# ProPrj_2025f4_025-07-20.net
KiCad netlist of a schematic drawn in EasyEDA Pro
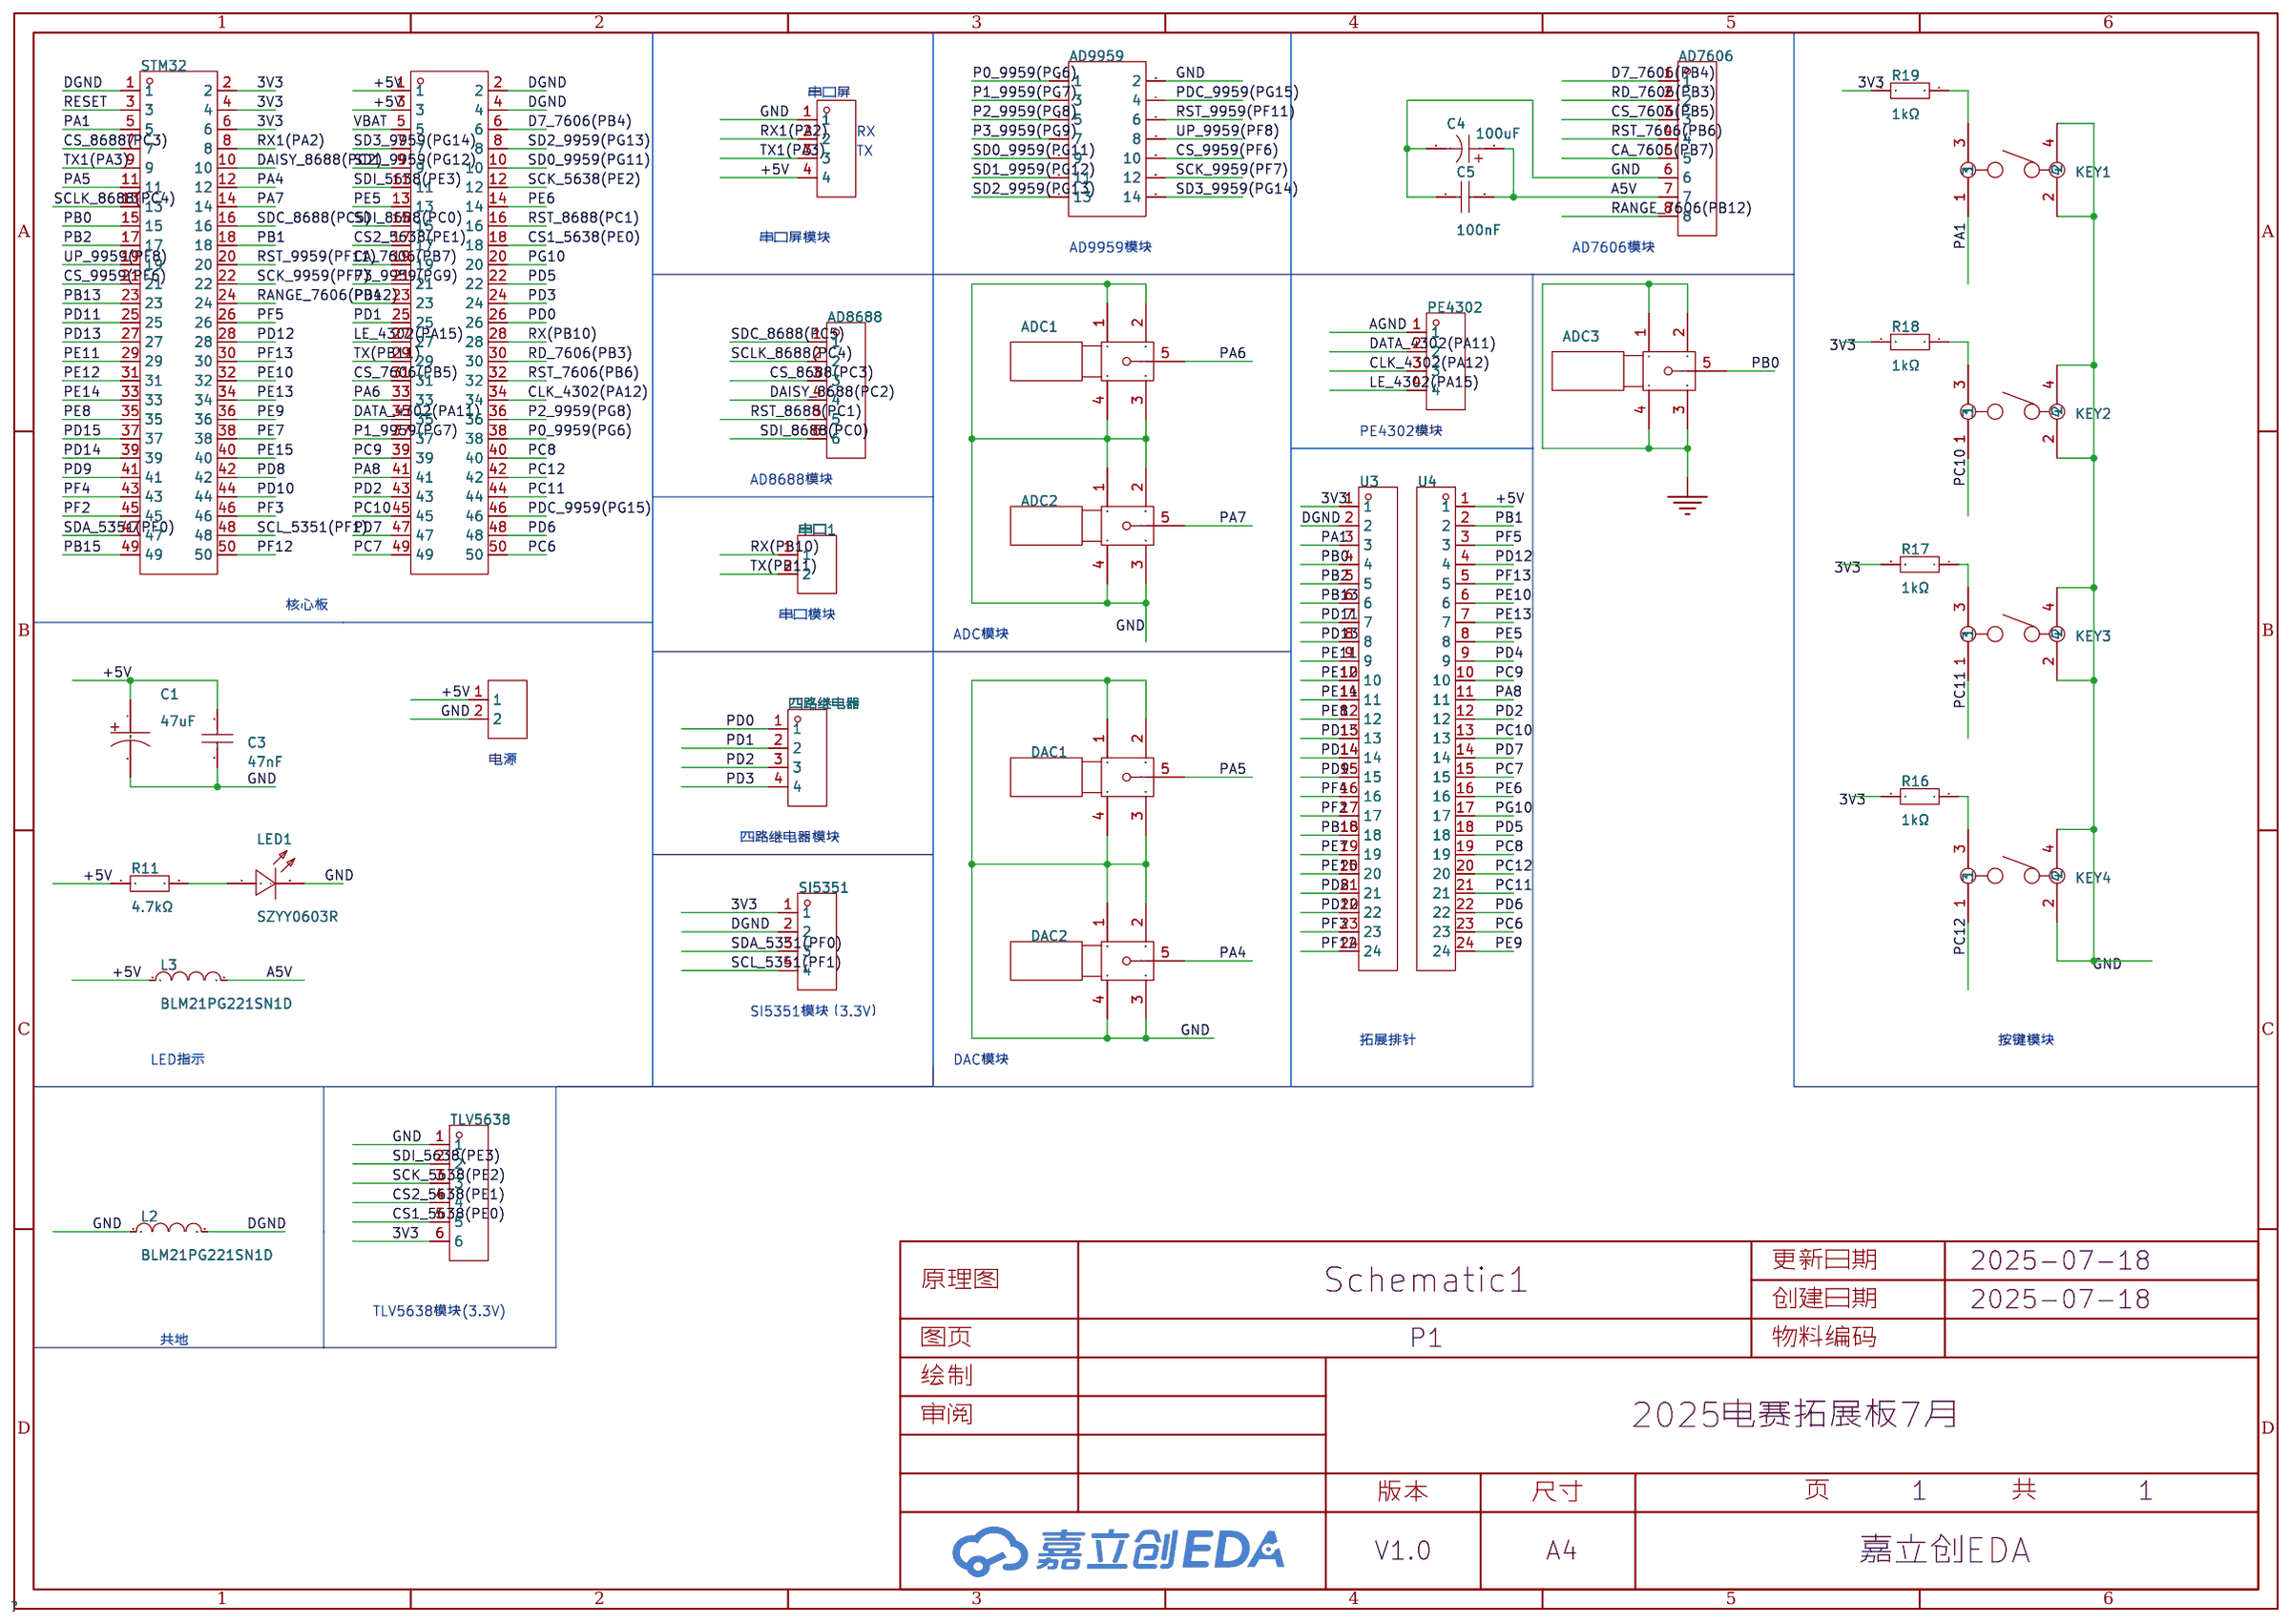
[diagram p0: schematic sheet]

(export (version "E")
  (design (tool "Eeschema 10.0.6"))
  (components
    (comp (ref "AD7606")
      (value "ZX-XH2.54-8PZZ")
      (footprint "easyedapro:CONN-TH_8P-P2.50-XH2.54-8P")
      (fields (field (name "Manufacturer") "Megastar(兆星)"))
      (libsource (lib "easyedapro") (part "ZX-XH2.54-8PZZ"))
    )
    (comp (ref "AD8688")
      (value "ZX-XH2.54-6PZZ")
      (footprint "easyedapro:CONN-TH_6P-P2.50_ZX-XH2.54-6PZZ")
      (fields (field (name "Manufacturer") "Megastar(兆星)"))
      (libsource (lib "easyedapro") (part "ZX-XH2.54-6PZZ"))
    )
    (comp (ref "AD9959")
      (value "2.54-2*7P简牛")
      (footprint "easyedapro:IDC-TH_14P-P2.54-V-R2-C7-S2.54")
      (description "连接器类型:简牛座;间距:2.54mm;结构:2x7P;封装形式:直插;行距:2.54mm;排数:2;每排PIN数:7;触头材质:黄铜;触头镀层:金;")
      (fields (field (name "Manufacturer") "BOOMELE(博穆精密)"))
      (libsource (lib "easyedapro") (part "HDR-IDC-2.54-2X7P"))
    )
    (comp (ref "ADC1")
      (value "BWSMA-KE-P001")
      (footprint "easyedapro:SMA-SMD_BWSMA-KE-P001")
      (description "连接器类型:板端;接口类型:内孔;端口数量:1;接口直径:5.2mm;接口长度/高度:-;频率-最大值:-;射频系列:SMA;阻抗:50Ω;样式:偏脚;工作温度范围:-;")
      (fields (field (name "Manufacturer") "BAT WIRELESS(蝙蝠无线)"))
      (libsource (lib "easyedapro") (part "BWSMA-KE-P001"))
    )
    (comp (ref "ADC2")
      (value "BWSMA-KE-P001")
      (footprint "easyedapro:SMA-SMD_BWSMA-KE-P001")
      (description "连接器类型:板端;接口类型:内孔;端口数量:1;接口直径:5.2mm;接口长度/高度:-;频率-最大值:-;射频系列:SMA;阻抗:50Ω;样式:偏脚;工作温度范围:-;")
      (fields (field (name "Manufacturer") "BAT WIRELESS(蝙蝠无线)"))
      (libsource (lib "easyedapro") (part "BWSMA-KE-P001"))
    )
    (comp (ref "ADC3")
      (value "BWSMA-KE-P001")
      (footprint "easyedapro:SMA-SMD_BWSMA-KE-P001")
      (description "连接器类型:板端;接口类型:内孔;端口数量:1;接口直径:5.2mm;接口长度/高度:-;频率-最大值:-;射频系列:SMA;阻抗:50Ω;样式:偏脚;工作温度范围:-;")
      (fields (field (name "Manufacturer") "BAT WIRELESS(蝙蝠无线)"))
      (libsource (lib "easyedapro") (part "BWSMA-KE-P001"))
    )
    (comp (ref "C1")
      (value "47uF")
      (footprint "easyedapro:CAP-TH_BD5.0-P2.00-D0.8-FD")
      (description "容值:47uF;精度:±20%;额定电压:25V;纹波电流:250mA@100kHz;等效串联电阻(ESR):300mΩ@100kHz;")
      (fields
        (field (name "Manufacturer Part") "NXB25V47M5*11 2.5TP")
        (field (name "Manufacturer") "SAMYOUNG(韩国三莹)")
      )
      (libsource (lib "easyedapro") (part "NXB25VB47M5*11_2.5TP"))
    )
    (comp (ref "C3")
      (value "47nF")
      (footprint "easyedapro:C0805")
      (description "容值:47nF;精度:±10%;额定电压:50V;材质(温度系数):X7R;")
      (fields
        (field (name "Manufacturer Part") "CL21B473KBCNNNC")
        (field (name "Manufacturer") "SAMSUNG(三星)")
      )
      (libsource (lib "easyedapro") (part "CL21B473KBCNNNC"))
    )
    (comp (ref "C4")
      (value "100uF")
      (footprint "easyedapro:CAP-TH_BD8.0-P3.50-D0.5-FD")
      (description "容值:100uF;精度:±20%;额定电压:50V;纹波电流:680mA@120Hz;等效串联电阻(ESR):120mΩ;")
      (fields (field (name "Manufacturer Part") "ERG50V100M8X12") (field (name "Manufacturer") "捷而瑞"))
      (libsource (lib "easyedapro") (part "ERG50V100M8X12"))
    )
    (comp (ref "C5")
      (value "100nF")
      (footprint "easyedapro:C0805")
      (description "容值:100nF;精度:±10%;额定电压:50V;材质(温度系数):X7R;")
      (fields
        (field (name "Manufacturer Part") "CL21B104KBCNNNC")
        (field (name "Manufacturer") "SAMSUNG(三星)")
      )
      (libsource (lib "easyedapro") (part "CL21B104KBCNNNC"))
    )
    (comp (ref "DAC1")
      (value "BWSMA-KE-P001")
      (footprint "easyedapro:SMA-SMD_BWSMA-KE-P001")
      (description "连接器类型:板端;接口类型:内孔;端口数量:1;接口直径:5.2mm;接口长度/高度:-;频率-最大值:-;射频系列:SMA;阻抗:50Ω;样式:偏脚;工作温度范围:-;")
      (fields (field (name "Manufacturer") "BAT WIRELESS(蝙蝠无线)"))
      (libsource (lib "easyedapro") (part "BWSMA-KE-P001"))
    )
    (comp (ref "DAC2")
      (value "BWSMA-KE-P001")
      (footprint "easyedapro:SMA-SMD_BWSMA-KE-P001")
      (description "连接器类型:板端;接口类型:内孔;端口数量:1;接口直径:5.2mm;接口长度/高度:-;频率-最大值:-;射频系列:SMA;阻抗:50Ω;样式:偏脚;工作温度范围:-;")
      (fields (field (name "Manufacturer") "BAT WIRELESS(蝙蝠无线)"))
      (libsource (lib "easyedapro") (part "BWSMA-KE-P001"))
    )
    (comp (ref "KEY1")
      (value "~")
      (footprint "easyedapro:4角直插式开关")
      (description "4.5*4.5*3.8")
      (libsource (lib "easyedapro") (part "4角直插式开关"))
    )
    (comp (ref "KEY2")
      (value "~")
      (footprint "easyedapro:4角直插式开关")
      (description "4.5*4.5*3.8")
      (libsource (lib "easyedapro") (part "4角直插式开关"))
    )
    (comp (ref "KEY3")
      (value "~")
      (footprint "easyedapro:4角直插式开关")
      (description "4.5*4.5*3.8")
      (libsource (lib "easyedapro") (part "4角直插式开关"))
    )
    (comp (ref "KEY4")
      (value "~")
      (footprint "easyedapro:4角直插式开关")
      (description "4.5*4.5*3.8")
      (libsource (lib "easyedapro") (part "4角直插式开关"))
    )
    (comp (ref "L2")
      (value "BLM21PG221SN1D")
      (footprint "easyedapro:L0805")
      (description "标称阻抗@测试频率:220Ω@100MHz;误差:±25%;直流电阻(RDC):45mΩ;")
      (fields (field (name "Manufacturer") "muRata(村田)"))
      (libsource (lib "easyedapro") (part "BLM21PG221SN1D"))
    )
    (comp (ref "L3")
      (value "BLM21PG221SN1D")
      (footprint "easyedapro:L0805")
      (description "标称阻抗@测试频率:220Ω@100MHz;误差:±25%;直流电阻(RDC):45mΩ;")
      (fields (field (name "Manufacturer") "muRata(村田)"))
      (libsource (lib "easyedapro") (part "BLM21PG221SN1D"))
    )
    (comp (ref "LED1")
      (value "SZYY0603R")
      (footprint "easyedapro:LED0603-R-RD")
      (fields (field (name "Manufacturer") "yongyu(永裕光电)"))
      (libsource (lib "easyedapro") (part "SZYY0603R"))
    )
    (comp (ref "OLED显示屏模块2")
      (value "ZX-XH2.54-4PZZ")
      (footprint "easyedapro:CONN-TH_4P-P2.50_4PIN")
      (fields (field (name "Manufacturer") "Megastar(兆星)"))
      (libsource (lib "easyedapro") (part "ZX-XH2.54-4PZZ"))
    )
    (comp (ref "PE4302")
      (value "ZX-XH2.54-4PZZ")
      (footprint "easyedapro:CONN-TH_4P-P2.50_4PIN")
      (fields (field (name "Manufacturer") "Megastar(兆星)"))
      (libsource (lib "easyedapro") (part "ZX-XH2.54-4PZZ"))
    )
    (comp (ref "R11")
      (value "4.7kΩ")
      (footprint "easyedapro:R0805")
      (description "电阻类型:厚膜电阻;阻值:4.7kΩ;精度:±1%;功率:125mW;最大工作电压:150V;温度系数:±100ppm/°C;")
      (fields
        (field (name "Manufacturer Part") "0805W8F4701T5E")
        (field (name "Manufacturer") "UNI-ROYAL(厚声)")
      )
      (libsource (lib "easyedapro") (part "0805W8F4701T5E"))
    )
    (comp (ref "R16")
      (value "1kΩ")
      (footprint "easyedapro:R0805")
      (description "电阻类型:厚膜电阻;阻值:1kΩ;精度:±1%;功率:125mW;温度系数:±100ppm/°C;最大工作电压:150V;工作温度范围:-55°C~+155°C;")
      (fields
        (field (name "Manufacturer Part") "0805W8F1001T5E")
        (field (name "Manufacturer") "UNI-ROYAL(厚声)")
      )
      (libsource (lib "easyedapro") (part "0805W8F1001T5E"))
    )
    (comp (ref "R17")
      (value "1kΩ")
      (footprint "easyedapro:R0805")
      (description "电阻类型:厚膜电阻;阻值:1kΩ;精度:±1%;功率:125mW;温度系数:±100ppm/°C;最大工作电压:150V;工作温度范围:-55°C~+155°C;")
      (fields
        (field (name "Manufacturer Part") "0805W8F1001T5E")
        (field (name "Manufacturer") "UNI-ROYAL(厚声)")
      )
      (libsource (lib "easyedapro") (part "0805W8F1001T5E"))
    )
    (comp (ref "R18")
      (value "1kΩ")
      (footprint "easyedapro:R0805")
      (description "电阻类型:厚膜电阻;阻值:1kΩ;精度:±1%;功率:125mW;温度系数:±100ppm/°C;最大工作电压:150V;工作温度范围:-55°C~+155°C;")
      (fields
        (field (name "Manufacturer Part") "0805W8F1001T5E")
        (field (name "Manufacturer") "UNI-ROYAL(厚声)")
      )
      (libsource (lib "easyedapro") (part "0805W8F1001T5E"))
    )
    (comp (ref "R19")
      (value "1kΩ")
      (footprint "easyedapro:R0805")
      (description "电阻类型:厚膜电阻;阻值:1kΩ;精度:±1%;功率:125mW;温度系数:±100ppm/°C;最大工作电压:150V;工作温度范围:-55°C~+155°C;")
      (fields
        (field (name "Manufacturer Part") "0805W8F1001T5E")
        (field (name "Manufacturer") "UNI-ROYAL(厚声)")
      )
      (libsource (lib "easyedapro") (part "0805W8F1001T5E"))
    )
    (comp (ref "SI5351")
      (value "ZX-XH2.54-4PZZ")
      (footprint "easyedapro:CONN-TH_4P-P2.50_4PIN")
      (fields (field (name "Manufacturer") "Megastar(兆星)"))
      (libsource (lib "easyedapro") (part "ZX-XH2.54-4PZZ"))
    )
    (comp (ref "STM32")
      (value "ZX-PM2.54-2-25PY")
      (footprint "easyedapro:HDR-TH_50P-P2.54-V-F-R2-C25-S2.54-1")
      (fields (field (name "Manufacturer") "Megastar(兆星)"))
      (libsource (lib "easyedapro") (part "ZX-PM2.54-2-25PY"))
    )
    (comp (ref "TLV5638")
      (value "ZX-XH2.54-6PZZ")
      (footprint "easyedapro:CONN-TH_6P-P2.50_ZX-XH2.54-6PZZ")
      (fields (field (name "Manufacturer") "Megastar(兆星)"))
      (libsource (lib "easyedapro") (part "ZX-XH2.54-6PZZ"))
    )
    (comp (ref "U2")
      (value "ZX-PM2.54-2-25PY")
      (footprint "easyedapro:HDR-TH_50P-P2.54-V-F-R2-C25-S2.54-1")
      (fields (field (name "Manufacturer") "Megastar(兆星)"))
      (libsource (lib "easyedapro") (part "ZX-PM2.54-2-25PY"))
    )
    (comp (ref "U3")
      (value "HC-PM254-8.5H-1x24PZ")
      (footprint "easyedapro:HDR-TH_24P-P2.54-V-F")
      (fields (field (name "Manufacturer") "HC(虹成电子)"))
      (libsource (lib "easyedapro") (part "HC-PM254-8.5H-1X24PZ"))
    )
    (comp (ref "U4")
      (value "HC-PM254-8.5H-1x24PZ")
      (footprint "easyedapro:HDR-TH_24P-P2.54-V-F")
      (fields (field (name "Manufacturer") "HC(虹成电子)"))
      (libsource (lib "easyedapro") (part "HC-PM254-8.5H-1X24PZ"))
    )
    (comp (ref "串口")
      (value "ZX-XH2.54-2PZZ")
      (footprint "easyedapro:CONN-TH_2P-P2.50_HX25003-2A")
      (fields (field (name "Manufacturer") "Megastar(兆星)"))
      (libsource (lib "easyedapro") (part "ZX-XH2.54-2PZZ"))
    )
    (comp (ref "串口1")
      (value "ZX-XH2.54-2PZZ")
      (footprint "easyedapro:CONN-TH_2P-P2.50_HX25003-2A")
      (fields (field (name "Manufacturer") "Megastar(兆星)"))
      (libsource (lib "easyedapro") (part "ZX-XH2.54-2PZZ"))
    )
    (comp (ref "四路继电器")
      (value "ZX-XH2.54-4PZZ")
      (footprint "easyedapro:CONN-TH_4P-P2.50_4PIN")
      (fields (field (name "Manufacturer") "Megastar(兆星)"))
      (libsource (lib "easyedapro") (part "ZX-XH2.54-4PZZ"))
    )
  )
  (nets
    (net (code "1") (name "/+5V") (class "Default")
      (node (ref "C1") (pin "1") (pinfunction "1_1") (pintype "unspecified"))
      (node (ref "C3") (pin "2") (pinfunction "2_2") (pintype "input"))
      (node (ref "L3") (pin "1") (pinfunction "1_1") (pintype "unspecified"))
      (node (ref "OLED显示屏模块2") (pin "4") (pinfunction "4_4") (pintype "unspecified"))
      (node (ref "R11") (pin "1") (pinfunction "1_1") (pintype "input"))
      (node (ref "U2") (pin "1") (pinfunction "1_1") (pintype "unspecified"))
      (node (ref "U2") (pin "3") (pinfunction "3_3") (pintype "unspecified"))
      (node (ref "U4") (pin "1") (pinfunction "1_1") (pintype "unspecified"))
      (node (ref "串口") (pin "1") (pinfunction "1_1") (pintype "unspecified"))
    )
    (net (code "2") (name "/3V3") (class "Default")
      (node (ref "R16") (pin "2") (pinfunction "2_2") (pintype "input"))
      (node (ref "R17") (pin "2") (pinfunction "2_2") (pintype "input"))
      (node (ref "R18") (pin "2") (pinfunction "2_2") (pintype "input"))
      (node (ref "R19") (pin "2") (pinfunction "2_2") (pintype "input"))
      (node (ref "SI5351") (pin "1") (pinfunction "1_1") (pintype "unspecified"))
      (node (ref "STM32") (pin "2") (pinfunction "2_2") (pintype "unspecified"))
      (node (ref "STM32") (pin "4") (pinfunction "4_4") (pintype "unspecified"))
      (node (ref "STM32") (pin "6") (pinfunction "6_6") (pintype "unspecified"))
      (node (ref "TLV5638") (pin "6") (pinfunction "6_6") (pintype "unspecified"))
      (node (ref "U3") (pin "1") (pinfunction "1_1") (pintype "unspecified"))
    )
    (net (code "3") (name "/A5V") (class "Default")
      (node (ref "AD7606") (pin "7") (pinfunction "7_7") (pintype "unspecified"))
      (node (ref "C4") (pin "1") (pinfunction "1_1") (pintype "input"))
      (node (ref "C5") (pin "2") (pinfunction "2_2") (pintype "input"))
      (node (ref "L3") (pin "2") (pinfunction "2_2") (pintype "unspecified"))
    )
    (net (code "4") (name "/AGND") (class "Default")
      (node (ref "PE4302") (pin "1") (pinfunction "1_1") (pintype "unspecified"))
    )
    (net (code "5") (name "/CA_7606(PB7)") (class "Default")
      (node (ref "AD7606") (pin "5") (pinfunction "5_5") (pintype "unspecified"))
      (node (ref "U2") (pin "19") (pinfunction "19_19") (pintype "unspecified"))
    )
    (net (code "6") (name "/CLK_4302(PA12)") (class "Default")
      (node (ref "PE4302") (pin "3") (pinfunction "3_3") (pintype "unspecified"))
      (node (ref "U2") (pin "34") (pinfunction "34_34") (pintype "unspecified"))
    )
    (net (code "7") (name "/CS1_5638(PE0)") (class "Default")
      (node (ref "TLV5638") (pin "5") (pinfunction "5_5") (pintype "unspecified"))
      (node (ref "U2") (pin "18") (pinfunction "18_18") (pintype "unspecified"))
    )
    (net (code "8") (name "/CS2_5638(PE1)") (class "Default")
      (node (ref "TLV5638") (pin "4") (pinfunction "4_4") (pintype "unspecified"))
      (node (ref "U2") (pin "17") (pinfunction "17_17") (pintype "unspecified"))
    )
    (net (code "9") (name "/CS_7606(PB5)") (class "Default")
      (node (ref "AD7606") (pin "3") (pinfunction "3_3") (pintype "unspecified"))
      (node (ref "U2") (pin "31") (pinfunction "31_31") (pintype "unspecified"))
    )
    (net (code "10") (name "/CS_8688(PC3)") (class "Default")
      (node (ref "AD8688") (pin "3") (pinfunction "3_3") (pintype "unspecified"))
      (node (ref "STM32") (pin "7") (pinfunction "7_7") (pintype "unspecified"))
    )
    (net (code "11") (name "/CS_9959(PF6)") (class "Default")
      (node (ref "AD9959") (pin "10") (pinfunction "10_10") (pintype "unspecified"))
      (node (ref "STM32") (pin "21") (pinfunction "21_21") (pintype "unspecified"))
    )
    (net (code "12") (name "/D7_7606(PB4)") (class "Default")
      (node (ref "AD7606") (pin "1") (pinfunction "1_1") (pintype "unspecified"))
      (node (ref "U2") (pin "6") (pinfunction "6_6") (pintype "unspecified"))
    )
    (net (code "13") (name "/DAISY_8688(PC2)") (class "Default")
      (node (ref "AD8688") (pin "4") (pinfunction "4_4") (pintype "unspecified"))
      (node (ref "STM32") (pin "10") (pinfunction "10_10") (pintype "unspecified"))
    )
    (net (code "14") (name "/DATA_4302(PA11)") (class "Default")
      (node (ref "PE4302") (pin "2") (pinfunction "2_2") (pintype "unspecified"))
      (node (ref "U2") (pin "35") (pinfunction "35_35") (pintype "unspecified"))
    )
    (net (code "15") (name "/DGND") (class "Default")
      (node (ref "L2") (pin "2") (pinfunction "2_2") (pintype "unspecified"))
      (node (ref "SI5351") (pin "2") (pinfunction "2_2") (pintype "unspecified"))
      (node (ref "STM32") (pin "1") (pinfunction "1_1") (pintype "unspecified"))
      (node (ref "U2") (pin "2") (pinfunction "2_2") (pintype "unspecified"))
      (node (ref "U2") (pin "4") (pinfunction "4_4") (pintype "unspecified"))
      (node (ref "U3") (pin "2") (pinfunction "2_2") (pintype "unspecified"))
    )
    (net (code "16") (name "/LE_4302(PA15)") (class "Default")
      (node (ref "PE4302") (pin "4") (pinfunction "4_4") (pintype "unspecified"))
      (node (ref "U2") (pin "27") (pinfunction "27_27") (pintype "unspecified"))
    )
    (net (code "17") (name "/P0_9959(PG6)") (class "Default")
      (node (ref "AD9959") (pin "1") (pinfunction "1_1") (pintype "unspecified"))
      (node (ref "U2") (pin "38") (pinfunction "38_38") (pintype "unspecified"))
    )
    (net (code "18") (name "/P1_9959(PG7)") (class "Default")
      (node (ref "AD9959") (pin "3") (pinfunction "3_3") (pintype "unspecified"))
      (node (ref "U2") (pin "37") (pinfunction "37_37") (pintype "unspecified"))
    )
    (net (code "19") (name "/P2_9959(PG8)") (class "Default")
      (node (ref "AD9959") (pin "5") (pinfunction "5_5") (pintype "unspecified"))
      (node (ref "U2") (pin "36") (pinfunction "36_36") (pintype "unspecified"))
    )
    (net (code "20") (name "/P3_9959(PG9)") (class "Default")
      (node (ref "AD9959") (pin "7") (pinfunction "7_7") (pintype "unspecified"))
      (node (ref "U2") (pin "21") (pinfunction "21_21") (pintype "unspecified"))
    )
    (net (code "21") (name "/PA1") (class "Default")
      (node (ref "KEY1") (pin "1") (pinfunction "1_1") (pintype "input"))
      (node (ref "STM32") (pin "5") (pinfunction "5_5") (pintype "unspecified"))
      (node (ref "U3") (pin "3") (pinfunction "3_3") (pintype "unspecified"))
    )
    (net (code "22") (name "/PA4") (class "Default")
      (node (ref "DAC2") (pin "5") (pinfunction "5_5") (pintype "unspecified"))
      (node (ref "STM32") (pin "12") (pinfunction "12_12") (pintype "unspecified"))
    )
    (net (code "23") (name "/PA5") (class "Default")
      (node (ref "DAC1") (pin "5") (pinfunction "5_5") (pintype "unspecified"))
      (node (ref "STM32") (pin "11") (pinfunction "11_11") (pintype "unspecified"))
    )
    (net (code "24") (name "/PA6") (class "Default")
      (node (ref "ADC1") (pin "5") (pinfunction "5_5") (pintype "unspecified"))
      (node (ref "U2") (pin "33") (pinfunction "33_33") (pintype "unspecified"))
    )
    (net (code "25") (name "/PA7") (class "Default")
      (node (ref "ADC2") (pin "5") (pinfunction "5_5") (pintype "unspecified"))
      (node (ref "STM32") (pin "14") (pinfunction "14_14") (pintype "unspecified"))
    )
    (net (code "26") (name "/PA8") (class "Default")
      (node (ref "U2") (pin "41") (pinfunction "41_41") (pintype "unspecified"))
      (node (ref "U4") (pin "11") (pinfunction "11_11") (pintype "unspecified"))
    )
    (net (code "27") (name "/PB0") (class "Default")
      (node (ref "ADC3") (pin "5") (pinfunction "5_5") (pintype "unspecified"))
      (node (ref "STM32") (pin "15") (pinfunction "15_15") (pintype "unspecified"))
      (node (ref "U3") (pin "4") (pinfunction "4_4") (pintype "unspecified"))
    )
    (net (code "28") (name "/PB1") (class "Default")
      (node (ref "STM32") (pin "18") (pinfunction "18_18") (pintype "unspecified"))
      (node (ref "U4") (pin "2") (pinfunction "2_2") (pintype "unspecified"))
    )
    (net (code "29") (name "/PB2") (class "Default")
      (node (ref "STM32") (pin "17") (pinfunction "17_17") (pintype "unspecified"))
      (node (ref "U3") (pin "5") (pinfunction "5_5") (pintype "unspecified"))
    )
    (net (code "30") (name "/PB13") (class "Default")
      (node (ref "STM32") (pin "23") (pinfunction "23_23") (pintype "unspecified"))
      (node (ref "U3") (pin "6") (pinfunction "6_6") (pintype "unspecified"))
    )
    (net (code "31") (name "/PB15") (class "Default")
      (node (ref "STM32") (pin "49") (pinfunction "49_49") (pintype "unspecified"))
      (node (ref "U3") (pin "18") (pinfunction "18_18") (pintype "unspecified"))
    )
    (net (code "32") (name "/PC6") (class "Default")
      (node (ref "U2") (pin "50") (pinfunction "50_50") (pintype "unspecified"))
      (node (ref "U4") (pin "23") (pinfunction "23_23") (pintype "unspecified"))
    )
    (net (code "33") (name "/PC7") (class "Default")
      (node (ref "U2") (pin "49") (pinfunction "49_49") (pintype "unspecified"))
      (node (ref "U4") (pin "15") (pinfunction "15_15") (pintype "unspecified"))
    )
    (net (code "34") (name "/PC8") (class "Default")
      (node (ref "U2") (pin "40") (pinfunction "40_40") (pintype "unspecified"))
      (node (ref "U4") (pin "19") (pinfunction "19_19") (pintype "unspecified"))
    )
    (net (code "35") (name "/PC9") (class "Default")
      (node (ref "U2") (pin "39") (pinfunction "39_39") (pintype "unspecified"))
      (node (ref "U4") (pin "10") (pinfunction "10_10") (pintype "unspecified"))
    )
    (net (code "36") (name "/PC10") (class "Default")
      (node (ref "KEY2") (pin "1") (pinfunction "1_1") (pintype "input"))
      (node (ref "U2") (pin "45") (pinfunction "45_45") (pintype "unspecified"))
      (node (ref "U4") (pin "13") (pinfunction "13_13") (pintype "unspecified"))
    )
    (net (code "37") (name "/PC11") (class "Default")
      (node (ref "KEY3") (pin "1") (pinfunction "1_1") (pintype "input"))
      (node (ref "U2") (pin "44") (pinfunction "44_44") (pintype "unspecified"))
      (node (ref "U4") (pin "21") (pinfunction "21_21") (pintype "unspecified"))
    )
    (net (code "38") (name "/PC12") (class "Default")
      (node (ref "KEY4") (pin "1") (pinfunction "1_1") (pintype "input"))
      (node (ref "U2") (pin "42") (pinfunction "42_42") (pintype "unspecified"))
      (node (ref "U4") (pin "20") (pinfunction "20_20") (pintype "unspecified"))
    )
    (net (code "39") (name "/PD0") (class "Default")
      (node (ref "U2") (pin "26") (pinfunction "26_26") (pintype "unspecified"))
      (node (ref "四路继电器") (pin "1") (pinfunction "1_1") (pintype "unspecified"))
    )
    (net (code "40") (name "/PD1") (class "Default")
      (node (ref "U2") (pin "25") (pinfunction "25_25") (pintype "unspecified"))
      (node (ref "四路继电器") (pin "2") (pinfunction "2_2") (pintype "unspecified"))
    )
    (net (code "41") (name "/PD2") (class "Default")
      (node (ref "U2") (pin "43") (pinfunction "43_43") (pintype "unspecified"))
      (node (ref "U4") (pin "12") (pinfunction "12_12") (pintype "unspecified"))
      (node (ref "四路继电器") (pin "3") (pinfunction "3_3") (pintype "unspecified"))
    )
    (net (code "42") (name "/PD3") (class "Default")
      (node (ref "U2") (pin "24") (pinfunction "24_24") (pintype "unspecified"))
      (node (ref "四路继电器") (pin "4") (pinfunction "4_4") (pintype "unspecified"))
    )
    (net (code "43") (name "/PD4") (class "Default")
      (node (ref "U2") (pin "23") (pinfunction "23_23") (pintype "unspecified"))
      (node (ref "U4") (pin "9") (pinfunction "9_9") (pintype "unspecified"))
    )
    (net (code "44") (name "/PD5") (class "Default")
      (node (ref "U2") (pin "22") (pinfunction "22_22") (pintype "unspecified"))
      (node (ref "U4") (pin "18") (pinfunction "18_18") (pintype "unspecified"))
    )
    (net (code "45") (name "/PD6") (class "Default")
      (node (ref "U2") (pin "48") (pinfunction "48_48") (pintype "unspecified"))
      (node (ref "U4") (pin "22") (pinfunction "22_22") (pintype "unspecified"))
    )
    (net (code "46") (name "/PD7") (class "Default")
      (node (ref "U2") (pin "47") (pinfunction "47_47") (pintype "unspecified"))
      (node (ref "U4") (pin "14") (pinfunction "14_14") (pintype "unspecified"))
    )
    (net (code "47") (name "/PD8") (class "Default")
      (node (ref "STM32") (pin "42") (pinfunction "42_42") (pintype "unspecified"))
      (node (ref "U3") (pin "21") (pinfunction "21_21") (pintype "unspecified"))
    )
    (net (code "48") (name "/PD9") (class "Default")
      (node (ref "STM32") (pin "41") (pinfunction "41_41") (pintype "unspecified"))
      (node (ref "U3") (pin "15") (pinfunction "15_15") (pintype "unspecified"))
    )
    (net (code "49") (name "/PD10") (class "Default")
      (node (ref "STM32") (pin "44") (pinfunction "44_44") (pintype "unspecified"))
      (node (ref "U3") (pin "22") (pinfunction "22_22") (pintype "unspecified"))
    )
    (net (code "50") (name "/PD11") (class "Default")
      (node (ref "STM32") (pin "25") (pinfunction "25_25") (pintype "unspecified"))
      (node (ref "U3") (pin "7") (pinfunction "7_7") (pintype "unspecified"))
    )
    (net (code "51") (name "/PD12") (class "Default")
      (node (ref "STM32") (pin "28") (pinfunction "28_28") (pintype "unspecified"))
      (node (ref "U4") (pin "4") (pinfunction "4_4") (pintype "unspecified"))
    )
    (net (code "52") (name "/PD13") (class "Default")
      (node (ref "STM32") (pin "27") (pinfunction "27_27") (pintype "unspecified"))
      (node (ref "U3") (pin "8") (pinfunction "8_8") (pintype "unspecified"))
    )
    (net (code "53") (name "/PD14") (class "Default")
      (node (ref "STM32") (pin "39") (pinfunction "39_39") (pintype "unspecified"))
      (node (ref "U3") (pin "14") (pinfunction "14_14") (pintype "unspecified"))
    )
    (net (code "54") (name "/PD15") (class "Default")
      (node (ref "STM32") (pin "37") (pinfunction "37_37") (pintype "unspecified"))
      (node (ref "U3") (pin "13") (pinfunction "13_13") (pintype "unspecified"))
    )
    (net (code "55") (name "/PDC_9959(PG15)") (class "Default")
      (node (ref "AD9959") (pin "4") (pinfunction "4_4") (pintype "unspecified"))
      (node (ref "U2") (pin "46") (pinfunction "46_46") (pintype "unspecified"))
    )
    (net (code "56") (name "/PE5") (class "Default")
      (node (ref "U2") (pin "13") (pinfunction "13_13") (pintype "unspecified"))
      (node (ref "U4") (pin "8") (pinfunction "8_8") (pintype "unspecified"))
    )
    (net (code "57") (name "/PE6") (class "Default")
      (node (ref "U2") (pin "14") (pinfunction "14_14") (pintype "unspecified"))
      (node (ref "U4") (pin "16") (pinfunction "16_16") (pintype "unspecified"))
    )
    (net (code "58") (name "/PE7") (class "Default")
      (node (ref "STM32") (pin "38") (pinfunction "38_38") (pintype "unspecified"))
      (node (ref "U3") (pin "19") (pinfunction "19_19") (pintype "unspecified"))
    )
    (net (code "59") (name "/PE8") (class "Default")
      (node (ref "STM32") (pin "35") (pinfunction "35_35") (pintype "unspecified"))
      (node (ref "U3") (pin "12") (pinfunction "12_12") (pintype "unspecified"))
    )
    (net (code "60") (name "/PE9") (class "Default")
      (node (ref "STM32") (pin "36") (pinfunction "36_36") (pintype "unspecified"))
      (node (ref "U4") (pin "24") (pinfunction "24_24") (pintype "unspecified"))
    )
    (net (code "61") (name "/PE10") (class "Default")
      (node (ref "STM32") (pin "32") (pinfunction "32_32") (pintype "unspecified"))
      (node (ref "U4") (pin "6") (pinfunction "6_6") (pintype "unspecified"))
    )
    (net (code "62") (name "/PE11") (class "Default")
      (node (ref "STM32") (pin "29") (pinfunction "29_29") (pintype "unspecified"))
      (node (ref "U3") (pin "9") (pinfunction "9_9") (pintype "unspecified"))
    )
    (net (code "63") (name "/PE12") (class "Default")
      (node (ref "STM32") (pin "31") (pinfunction "31_31") (pintype "unspecified"))
      (node (ref "U3") (pin "10") (pinfunction "10_10") (pintype "unspecified"))
    )
    (net (code "64") (name "/PE13") (class "Default")
      (node (ref "STM32") (pin "34") (pinfunction "34_34") (pintype "unspecified"))
      (node (ref "U4") (pin "7") (pinfunction "7_7") (pintype "unspecified"))
    )
    (net (code "65") (name "/PE14") (class "Default")
      (node (ref "STM32") (pin "33") (pinfunction "33_33") (pintype "unspecified"))
      (node (ref "U3") (pin "11") (pinfunction "11_11") (pintype "unspecified"))
    )
    (net (code "66") (name "/PE15") (class "Default")
      (node (ref "STM32") (pin "40") (pinfunction "40_40") (pintype "unspecified"))
      (node (ref "U3") (pin "20") (pinfunction "20_20") (pintype "unspecified"))
    )
    (net (code "67") (name "/PF2") (class "Default")
      (node (ref "STM32") (pin "45") (pinfunction "45_45") (pintype "unspecified"))
      (node (ref "U3") (pin "17") (pinfunction "17_17") (pintype "unspecified"))
    )
    (net (code "68") (name "/PF3") (class "Default")
      (node (ref "STM32") (pin "46") (pinfunction "46_46") (pintype "unspecified"))
      (node (ref "U3") (pin "23") (pinfunction "23_23") (pintype "unspecified"))
    )
    (net (code "69") (name "/PF4") (class "Default")
      (node (ref "STM32") (pin "43") (pinfunction "43_43") (pintype "unspecified"))
      (node (ref "U3") (pin "16") (pinfunction "16_16") (pintype "unspecified"))
    )
    (net (code "70") (name "/PF5") (class "Default")
      (node (ref "STM32") (pin "26") (pinfunction "26_26") (pintype "unspecified"))
      (node (ref "U4") (pin "3") (pinfunction "3_3") (pintype "unspecified"))
    )
    (net (code "71") (name "/PF12") (class "Default")
      (node (ref "STM32") (pin "50") (pinfunction "50_50") (pintype "unspecified"))
      (node (ref "U3") (pin "24") (pinfunction "24_24") (pintype "unspecified"))
    )
    (net (code "72") (name "/PF13") (class "Default")
      (node (ref "STM32") (pin "30") (pinfunction "30_30") (pintype "unspecified"))
      (node (ref "U4") (pin "5") (pinfunction "5_5") (pintype "unspecified"))
    )
    (net (code "73") (name "/PG10") (class "Default")
      (node (ref "U2") (pin "20") (pinfunction "20_20") (pintype "unspecified"))
      (node (ref "U4") (pin "17") (pinfunction "17_17") (pintype "unspecified"))
    )
    (net (code "74") (name "/RANGE_7606(PB12)") (class "Default")
      (node (ref "AD7606") (pin "8") (pinfunction "8_8") (pintype "unspecified"))
      (node (ref "STM32") (pin "24") (pinfunction "24_24") (pintype "unspecified"))
    )
    (net (code "75") (name "/RD_7606(PB3)") (class "Default")
      (node (ref "AD7606") (pin "2") (pinfunction "2_2") (pintype "unspecified"))
      (node (ref "U2") (pin "30") (pinfunction "30_30") (pintype "unspecified"))
    )
    (net (code "76") (name "/RESET") (class "Default")
      (node (ref "STM32") (pin "3") (pinfunction "3_3") (pintype "unspecified"))
    )
    (net (code "77") (name "/RST_7606(PB6)") (class "Default")
      (node (ref "AD7606") (pin "4") (pinfunction "4_4") (pintype "unspecified"))
      (node (ref "U2") (pin "32") (pinfunction "32_32") (pintype "unspecified"))
    )
    (net (code "78") (name "/RST_8688(PC1)") (class "Default")
      (node (ref "AD8688") (pin "5") (pinfunction "5_5") (pintype "unspecified"))
      (node (ref "U2") (pin "16") (pinfunction "16_16") (pintype "unspecified"))
    )
    (net (code "79") (name "/RST_9959(PF11)") (class "Default")
      (node (ref "AD9959") (pin "6") (pinfunction "6_6") (pintype "unspecified"))
      (node (ref "STM32") (pin "20") (pinfunction "20_20") (pintype "unspecified"))
    )
    (net (code "80") (name "/RX(PB10)") (class "Default")
      (node (ref "U2") (pin "28") (pinfunction "28_28") (pintype "unspecified"))
      (node (ref "串口1") (pin "1") (pinfunction "1_1") (pintype "unspecified"))
    )
    (net (code "81") (name "/RX1(PA2)") (class "Default")
      (node (ref "OLED显示屏模块2") (pin "2") (pinfunction "2_2") (pintype "unspecified"))
      (node (ref "STM32") (pin "8") (pinfunction "8_8") (pintype "unspecified"))
    )
    (net (code "82") (name "/SCK_5638(PE2)") (class "Default")
      (node (ref "TLV5638") (pin "3") (pinfunction "3_3") (pintype "unspecified"))
      (node (ref "U2") (pin "12") (pinfunction "12_12") (pintype "unspecified"))
    )
    (net (code "83") (name "/SCK_9959(PF7)") (class "Default")
      (node (ref "AD9959") (pin "12") (pinfunction "12_12") (pintype "unspecified"))
      (node (ref "STM32") (pin "22") (pinfunction "22_22") (pintype "unspecified"))
    )
    (net (code "84") (name "/SCLK_8688(PC4)") (class "Default")
      (node (ref "AD8688") (pin "2") (pinfunction "2_2") (pintype "unspecified"))
      (node (ref "STM32") (pin "13") (pinfunction "13_13") (pintype "unspecified"))
    )
    (net (code "85") (name "/SCL_5351(PF1)") (class "Default")
      (node (ref "SI5351") (pin "4") (pinfunction "4_4") (pintype "unspecified"))
      (node (ref "STM32") (pin "48") (pinfunction "48_48") (pintype "unspecified"))
    )
    (net (code "86") (name "/SD0_9959(PG11)") (class "Default")
      (node (ref "AD9959") (pin "9") (pinfunction "9_9") (pintype "unspecified"))
      (node (ref "U2") (pin "10") (pinfunction "10_10") (pintype "unspecified"))
    )
    (net (code "87") (name "/SD1_9959(PG12)") (class "Default")
      (node (ref "AD9959") (pin "11") (pinfunction "11_11") (pintype "unspecified"))
      (node (ref "U2") (pin "9") (pinfunction "9_9") (pintype "unspecified"))
    )
    (net (code "88") (name "/SD2_9959(PG13)") (class "Default")
      (node (ref "AD9959") (pin "13") (pinfunction "13_13") (pintype "unspecified"))
      (node (ref "U2") (pin "8") (pinfunction "8_8") (pintype "unspecified"))
    )
    (net (code "89") (name "/SD3_9959(PG14)") (class "Default")
      (node (ref "AD9959") (pin "14") (pinfunction "14_14") (pintype "unspecified"))
      (node (ref "U2") (pin "7") (pinfunction "7_7") (pintype "unspecified"))
    )
    (net (code "90") (name "/SDA_5351(PF0)") (class "Default")
      (node (ref "SI5351") (pin "3") (pinfunction "3_3") (pintype "unspecified"))
      (node (ref "STM32") (pin "47") (pinfunction "47_47") (pintype "unspecified"))
    )
    (net (code "91") (name "/SDC_8688(PC5)") (class "Default")
      (node (ref "AD8688") (pin "1") (pinfunction "1_1") (pintype "unspecified"))
      (node (ref "STM32") (pin "16") (pinfunction "16_16") (pintype "unspecified"))
    )
    (net (code "92") (name "/SDI_5638(PE3)") (class "Default")
      (node (ref "TLV5638") (pin "2") (pinfunction "2_2") (pintype "unspecified"))
      (node (ref "U2") (pin "11") (pinfunction "11_11") (pintype "unspecified"))
    )
    (net (code "93") (name "/SDI_8688(PC0)") (class "Default")
      (node (ref "AD8688") (pin "6") (pinfunction "6_6") (pintype "unspecified"))
      (node (ref "U2") (pin "15") (pinfunction "15_15") (pintype "unspecified"))
    )
    (net (code "94") (name "/TX(PB11)") (class "Default")
      (node (ref "U2") (pin "29") (pinfunction "29_29") (pintype "unspecified"))
      (node (ref "串口1") (pin "2") (pinfunction "2_2") (pintype "unspecified"))
    )
    (net (code "95") (name "/TX1(PA3)") (class "Default")
      (node (ref "OLED显示屏模块2") (pin "3") (pinfunction "3_3") (pintype "unspecified"))
      (node (ref "STM32") (pin "9") (pinfunction "9_9") (pintype "unspecified"))
    )
    (net (code "96") (name "/UP_9959(PF8)") (class "Default")
      (node (ref "AD9959") (pin "8") (pinfunction "8_8") (pintype "unspecified"))
      (node (ref "STM32") (pin "19") (pinfunction "19_19") (pintype "unspecified"))
    )
    (net (code "97") (name "/VBAT") (class "Default")
      (node (ref "U2") (pin "5") (pinfunction "5_5") (pintype "unspecified"))
    )
    (net (code "98") (name "GND") (class "Default")
      (node (ref "AD7606") (pin "6") (pinfunction "6_6") (pintype "unspecified"))
      (node (ref "AD9959") (pin "2") (pinfunction "2_2") (pintype "unspecified"))
      (node (ref "ADC1") (pin "1") (pinfunction "1_1") (pintype "unspecified"))
      (node (ref "ADC1") (pin "2") (pinfunction "2_2") (pintype "unspecified"))
      (node (ref "ADC1") (pin "3") (pinfunction "3_3") (pintype "unspecified"))
      (node (ref "ADC1") (pin "4") (pinfunction "4_4") (pintype "unspecified"))
      (node (ref "ADC2") (pin "1") (pinfunction "1_1") (pintype "unspecified"))
      (node (ref "ADC2") (pin "2") (pinfunction "2_2") (pintype "unspecified"))
      (node (ref "ADC2") (pin "3") (pinfunction "3_3") (pintype "unspecified"))
      (node (ref "ADC2") (pin "4") (pinfunction "4_4") (pintype "unspecified"))
      (node (ref "ADC3") (pin "1") (pinfunction "1_1") (pintype "unspecified"))
      (node (ref "ADC3") (pin "2") (pinfunction "2_2") (pintype "unspecified"))
      (node (ref "ADC3") (pin "3") (pinfunction "3_3") (pintype "unspecified"))
      (node (ref "ADC3") (pin "4") (pinfunction "4_4") (pintype "unspecified"))
      (node (ref "C1") (pin "2") (pinfunction "2_2") (pintype "unspecified"))
      (node (ref "C3") (pin "1") (pinfunction "1_1") (pintype "input"))
      (node (ref "C4") (pin "2") (pinfunction "2_2") (pintype "input"))
      (node (ref "C5") (pin "1") (pinfunction "1_1") (pintype "input"))
      (node (ref "DAC1") (pin "1") (pinfunction "1_1") (pintype "unspecified"))
      (node (ref "DAC1") (pin "2") (pinfunction "2_2") (pintype "unspecified"))
      (node (ref "DAC1") (pin "3") (pinfunction "3_3") (pintype "unspecified"))
      (node (ref "DAC1") (pin "4") (pinfunction "4_4") (pintype "unspecified"))
      (node (ref "DAC2") (pin "1") (pinfunction "1_1") (pintype "unspecified"))
      (node (ref "DAC2") (pin "2") (pinfunction "2_2") (pintype "unspecified"))
      (node (ref "DAC2") (pin "3") (pinfunction "3_3") (pintype "unspecified"))
      (node (ref "DAC2") (pin "4") (pinfunction "4_4") (pintype "unspecified"))
      (node (ref "KEY1") (pin "2") (pinfunction "2_2") (pintype "input"))
      (node (ref "KEY1") (pin "4") (pinfunction "4_4") (pintype "input"))
      (node (ref "KEY2") (pin "2") (pinfunction "2_2") (pintype "input"))
      (node (ref "KEY2") (pin "4") (pinfunction "4_4") (pintype "input"))
      (node (ref "KEY3") (pin "2") (pinfunction "2_2") (pintype "input"))
      (node (ref "KEY3") (pin "4") (pinfunction "4_4") (pintype "input"))
      (node (ref "KEY4") (pin "2") (pinfunction "2_2") (pintype "input"))
      (node (ref "KEY4") (pin "4") (pinfunction "4_4") (pintype "input"))
      (node (ref "L2") (pin "1") (pinfunction "1_1") (pintype "unspecified"))
      (node (ref "LED1") (pin "2") (pinfunction "-_2") (pintype "unspecified"))
      (node (ref "OLED显示屏模块2") (pin "1") (pinfunction "1_1") (pintype "unspecified"))
      (node (ref "TLV5638") (pin "1") (pinfunction "1_1") (pintype "unspecified"))
      (node (ref "串口") (pin "2") (pinfunction "2_2") (pintype "unspecified"))
    )
    (net (code "99") (name "Net-(KEY1-Pad3)") (class "Default")
      (node (ref "KEY1") (pin "3") (pinfunction "3_3") (pintype "input"))
      (node (ref "R19") (pin "1") (pinfunction "1_1") (pintype "input"))
    )
    (net (code "100") (name "Net-(KEY2-Pad3)") (class "Default")
      (node (ref "KEY2") (pin "3") (pinfunction "3_3") (pintype "input"))
      (node (ref "R18") (pin "1") (pinfunction "1_1") (pintype "input"))
    )
    (net (code "101") (name "Net-(KEY3-Pad3)") (class "Default")
      (node (ref "KEY3") (pin "3") (pinfunction "3_3") (pintype "input"))
      (node (ref "R17") (pin "1") (pinfunction "1_1") (pintype "input"))
    )
    (net (code "102") (name "Net-(KEY4-Pad3)") (class "Default")
      (node (ref "KEY4") (pin "3") (pinfunction "3_3") (pintype "input"))
      (node (ref "R16") (pin "1") (pinfunction "1_1") (pintype "input"))
    )
    (net (code "103") (name "Net-(LED1-+)") (class "Default")
      (node (ref "LED1") (pin "1") (pinfunction "+_1") (pintype "unspecified"))
      (node (ref "R11") (pin "2") (pinfunction "2_2") (pintype "input"))
    )
  )
)
